# InputChannel_1.net
KiCad netlist of a schematic drawn in Altium Designer
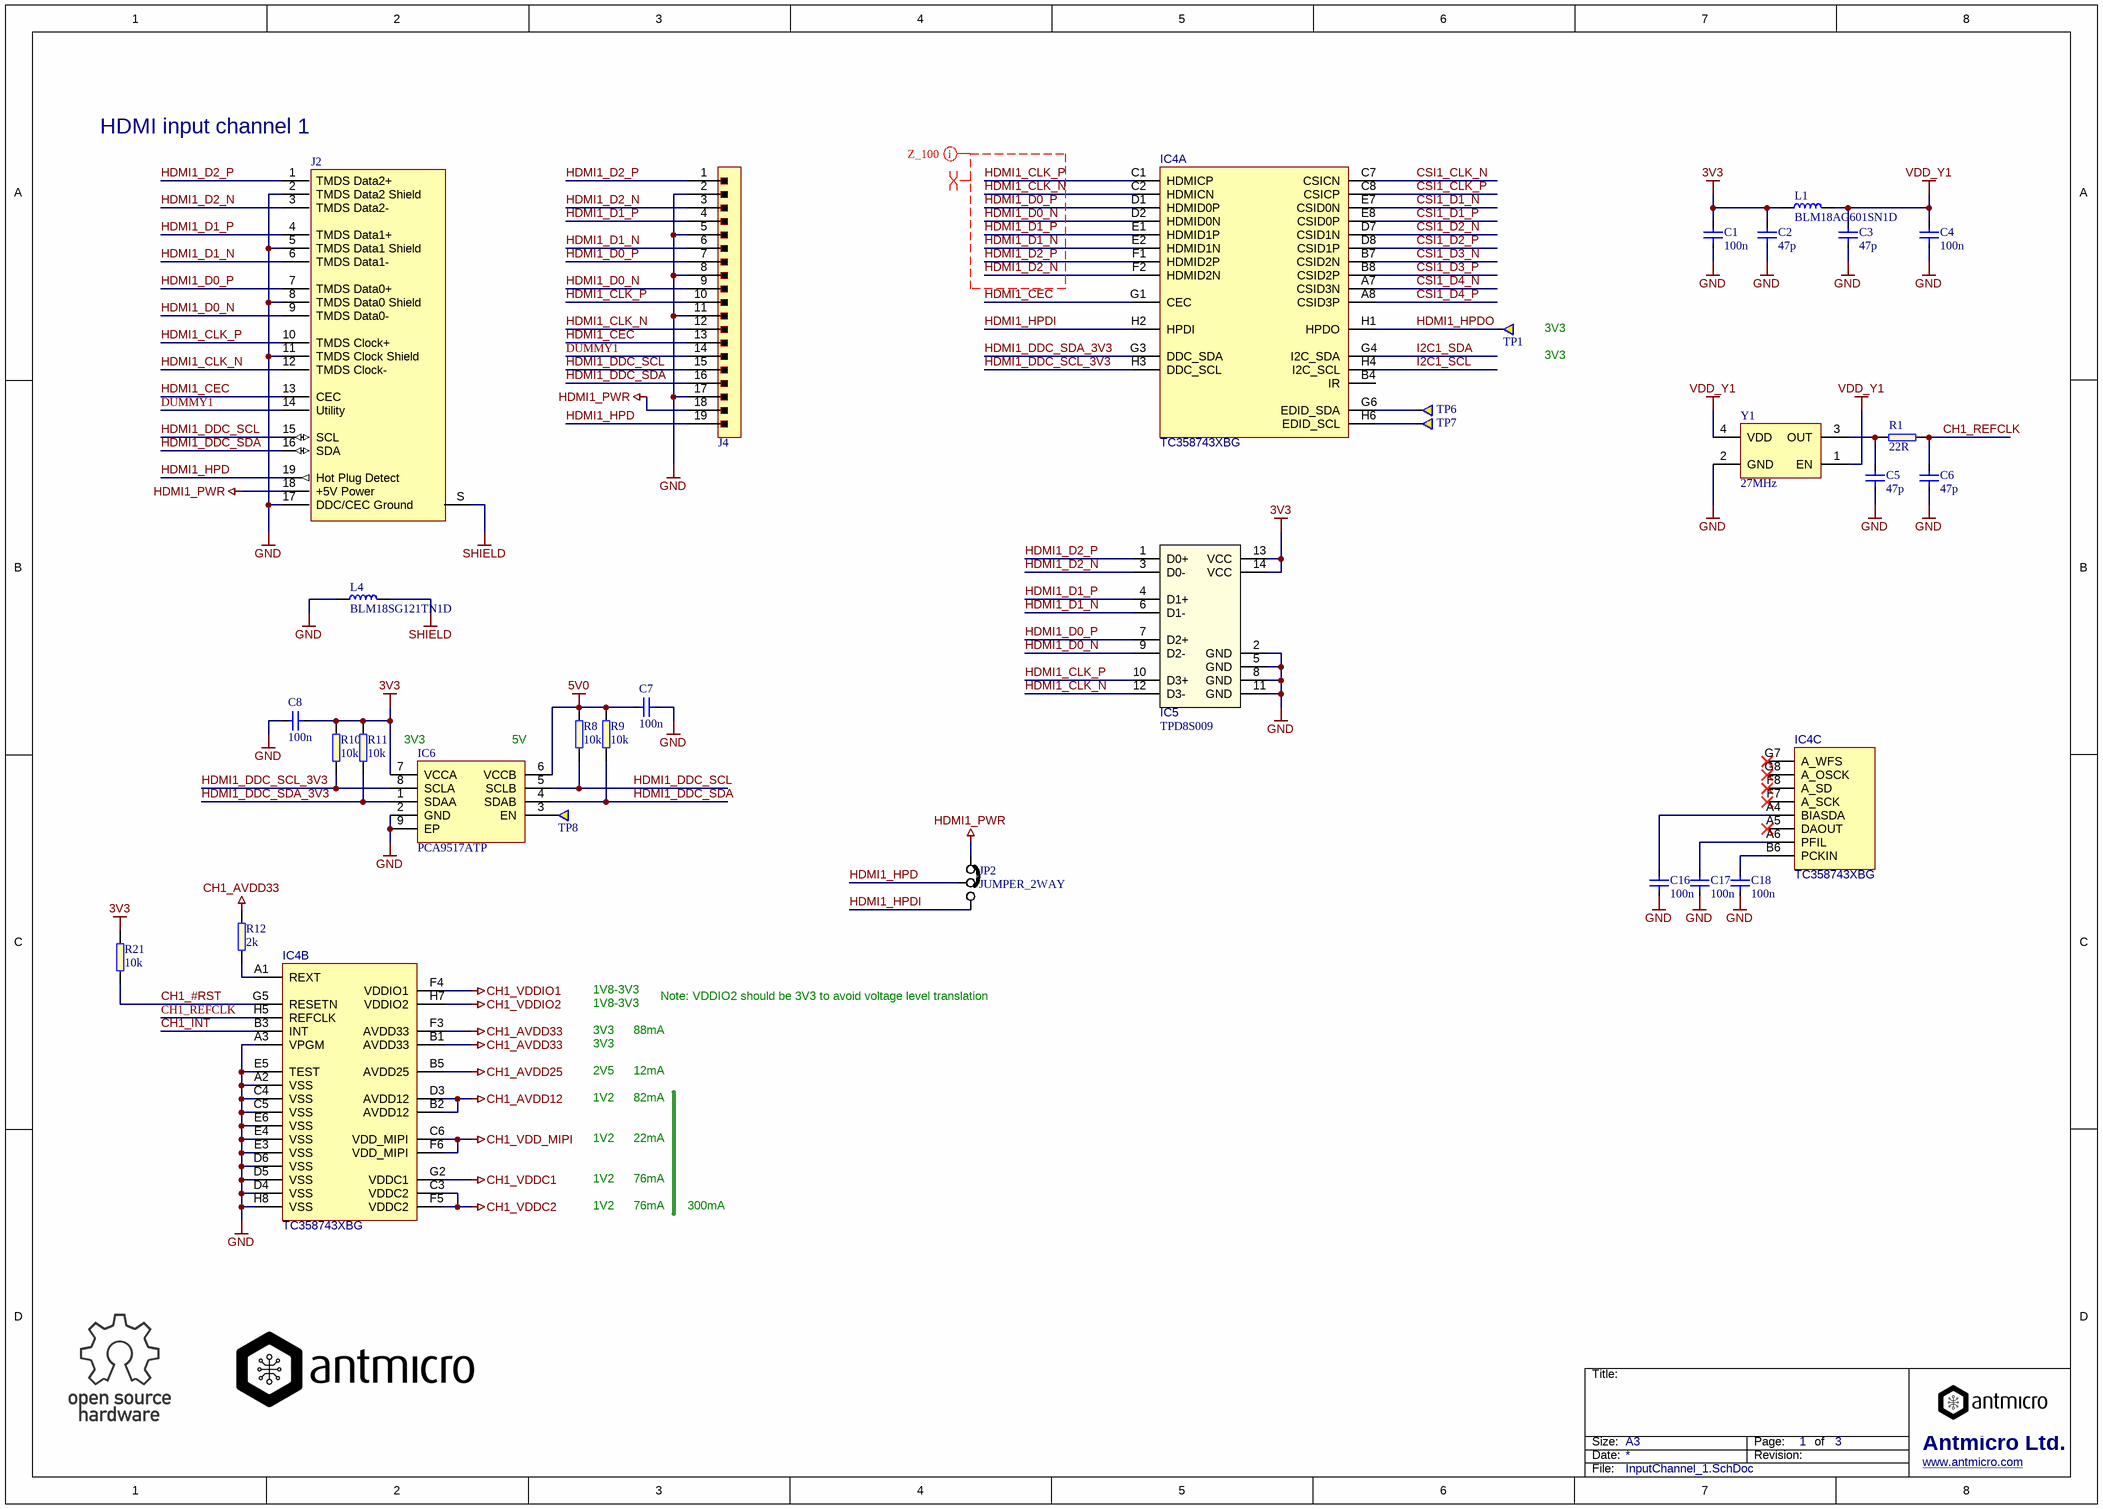
[diagram p0: InputChannel_1.SchDoc]

(export (version "E")
  (design (tool "Eeschema 10.0.6"))
  (components
    (comp (ref "C1")
      (value "100n")
      (footprint "HDMI-MIPI-Bridge:0402")
      (description "MLCC SMT Capacitor 100nF 0402")
      (fields (field (name "PART NUMBER") "C_100n_0402") (field (name "MANUFACTURER") "MULTICOMP"))
      (libsource (lib "AntmicroComponents") (part "C"))
    )
    (comp (ref "C2")
      (value "47p")
      (footprint "HDMI-MIPI-Bridge:0402")
      (description "MLCC SMT Capacitor 47pF 0402")
      (fields (field (name "PART NUMBER") "C_47p_0402") (field (name "MANUFACTURER") "KEMET"))
      (libsource (lib "AntmicroComponents") (part "C"))
    )
    (comp (ref "C3")
      (value "47p")
      (footprint "HDMI-MIPI-Bridge:0402")
      (description "MLCC SMT Capacitor 47pF 0402")
      (fields (field (name "PART NUMBER") "C_47p_0402") (field (name "MANUFACTURER") "KEMET"))
      (libsource (lib "AntmicroComponents") (part "C"))
    )
    (comp (ref "C4")
      (value "100n")
      (footprint "HDMI-MIPI-Bridge:0402")
      (description "MLCC SMT Capacitor 100nF 0402")
      (fields (field (name "PART NUMBER") "C_100n_0402") (field (name "MANUFACTURER") "MULTICOMP"))
      (libsource (lib "AntmicroComponents") (part "C"))
    )
    (comp (ref "C5")
      (value "47p")
      (footprint "HDMI-MIPI-Bridge:0402")
      (description "MLCC SMT Capacitor 47pF 0402")
      (fields (field (name "PART NUMBER") "C_47p_0402") (field (name "MANUFACTURER") "KEMET"))
      (libsource (lib "AntmicroComponents") (part "C"))
    )
    (comp (ref "C6")
      (value "47p")
      (footprint "HDMI-MIPI-Bridge:0402")
      (description "MLCC SMT Capacitor 47pF 0402")
      (fields (field (name "PART NUMBER") "C_47p_0402") (field (name "MANUFACTURER") "KEMET"))
      (libsource (lib "AntmicroComponents") (part "C"))
    )
    (comp (ref "C7")
      (value "100n")
      (footprint "HDMI-MIPI-Bridge:0402")
      (description "MLCC SMT Capacitor 100nF 0402")
      (fields (field (name "PART NUMBER") "C_100n_0402") (field (name "MANUFACTURER") "MULTICOMP"))
      (libsource (lib "AntmicroComponents") (part "C"))
    )
    (comp (ref "C8")
      (value "100n")
      (footprint "HDMI-MIPI-Bridge:0402")
      (description "MLCC SMT Capacitor 100nF 0402")
      (fields (field (name "PART NUMBER") "C_100n_0402") (field (name "MANUFACTURER") "MULTICOMP"))
      (libsource (lib "AntmicroComponents") (part "C"))
    )
    (comp (ref "C16")
      (value "100n")
      (footprint "HDMI-MIPI-Bridge:0402")
      (description "MLCC SMT Capacitor 100nF 0402")
      (fields (field (name "PART NUMBER") "C_100n_0402") (field (name "MANUFACTURER") "MULTICOMP"))
      (libsource (lib "AntmicroComponents") (part "C"))
    )
    (comp (ref "C17")
      (value "100n")
      (footprint "HDMI-MIPI-Bridge:0402")
      (description "MLCC SMT Capacitor 100nF 0402")
      (fields (field (name "PART NUMBER") "C_100n_0402") (field (name "MANUFACTURER") "MULTICOMP"))
      (libsource (lib "AntmicroComponents") (part "C"))
    )
    (comp (ref "C18")
      (value "100n")
      (footprint "HDMI-MIPI-Bridge:0402")
      (description "MLCC SMT Capacitor 100nF 0402")
      (fields (field (name "PART NUMBER") "C_100n_0402") (field (name "MANUFACTURER") "MULTICOMP"))
      (libsource (lib "AntmicroComponents") (part "C"))
    )
    (comp (ref "IC4")
      (value "TC358743XBG")
      (footprint "HDMI-MIPI-Bridge:TC358743XBG")
      (description "Toshiba TC358743XBG HDMI-CSI bridge")
      (fields (field (name "MANUFACTURER") "Toshiba"))
      (libsource (lib "AntmicroComponents") (part "TC358743XBG"))
    )
    (comp (ref "IC5")
      (value "TPD8S009")
      (footprint "HDMI-MIPI-Bridge:SON-15")
      (description "8-Channel ESD Protection for DisplayPort and HDMI")
      (fields (field (name "MANUFACTURER") "TEXAS INSTRUMENTS") (field (name "MPN") "TPD8S009DSMR"))
      (libsource (lib "AntmicroComponents") (part "TPD8S009"))
    )
    (comp (ref "IC6")
      (value "PCA9517ATP")
      (footprint "HDMI-MIPI-Bridge:PCA9517ATP")
      (description "I2C BUS REPEATER W/ LEVEL TRANS, HWSON-8")
      (fields (field (name "MANUFACTURER") "NXP"))
      (libsource (lib "AntmicroComponents") (part "PCA9517ATP"))
    )
    (comp (ref "J2")
      (value "~")
      (footprint "HDMI-MIPI-Bridge:Molex_HDMI_471511001")
      (description "Header right angle HDMI")
      (fields (field (name "PART NUMBER") "CON-Molex-471511001") (field (name "MANUFACTURER") "MOLEX"))
      (libsource (lib "AntmicroComponents") (part "CON-Molex-471511001"))
    )
    (comp (ref "J4")
      (value "Molex-505110-1992")
      (footprint "HDMI-MIPI-Bridge:CON-Molex-505110-1992")
      (description "FPC socket 19 pins")
      (fields (field (name "PART NUMBER") "CON-Molex-505110-1992") (field (name "MANUFACTURER") "Molex"))
      (libsource (lib "AntmicroComponents") (part "1X19"))
    )
    (comp (ref "JP2")
      (value "JUMPER_2WAY")
      (footprint "HDMI-MIPI-Bridge:JUMPER_2WAY")
      (description "Solder jumper")
      (fields (field (name "PART NUMBER") "Jumper 2 way"))
      (libsource (lib "AntmicroComponents") (part "JUMPER_2WAY"))
    )
    (comp (ref "L1")
      (value "BLM18AG601SN1D")
      (footprint "HDMI-MIPI-Bridge:0603")
      (description "Ferrite Bead, 600 ohm, 0603 [1608 Metric], BLM18A Series, 500 mA, 0.38 ohm, ± 25%")
      (fields (field (name "MANUFACTURER") "MURATA"))
      (libsource (lib "AntmicroComponents") (part "Inductor SMT"))
    )
    (comp (ref "L4")
      (value "BLM18SG121TN1D")
      (footprint "HDMI-MIPI-Bridge:0603")
      (description "FERRITE BEAD, 0.025OHM, 3A, 0603")
      (fields (field (name "MANUFACTURER") "MURATA"))
      (libsource (lib "AntmicroComponents") (part "Inductor SMT"))
    )
    (comp (ref "R1")
      (value "22R")
      (footprint "HDMI-MIPI-Bridge:0402")
      (description "SMT Resistor 22R 0402")
      (fields (field (name "PART NUMBER") "R_22R_0402") (field (name "MANUFACTURER") "VISHAY"))
      (libsource (lib "") (part "R_1"))
    )
    (comp (ref "R8")
      (value "10k")
      (footprint "HDMI-MIPI-Bridge:0402")
      (description "SMT Resistor 0402")
      (fields (field (name "PART NUMBER") "R_10k_0402") (field (name "MANUFACTURER") "MULTICOMP"))
      (libsource (lib "AntmicroComponents") (part "R"))
    )
    (comp (ref "R9")
      (value "10k")
      (footprint "HDMI-MIPI-Bridge:0402")
      (description "SMT Resistor 0402")
      (fields (field (name "PART NUMBER") "R_10k_0402") (field (name "MANUFACTURER") "MULTICOMP"))
      (libsource (lib "AntmicroComponents") (part "R"))
    )
    (comp (ref "R10")
      (value "10k")
      (footprint "HDMI-MIPI-Bridge:0402")
      (description "SMT Resistor 0402")
      (fields (field (name "PART NUMBER") "R_10k_0402") (field (name "MANUFACTURER") "MULTICOMP"))
      (libsource (lib "AntmicroComponents") (part "R"))
    )
    (comp (ref "R11")
      (value "10k")
      (footprint "HDMI-MIPI-Bridge:0402")
      (description "SMT Resistor 0402")
      (fields (field (name "PART NUMBER") "R_10k_0402") (field (name "MANUFACTURER") "MULTICOMP"))
      (libsource (lib "AntmicroComponents") (part "R"))
    )
    (comp (ref "R12")
      (value "2k")
      (footprint "HDMI-MIPI-Bridge:0603")
      (description "SMT Resistor 2k 0603")
      (fields (field (name "PART NUMBER") "R_2k_0603") (field (name "MANUFACTURER") "MULTICOMP"))
      (libsource (lib "AntmicroComponents") (part "R"))
    )
    (comp (ref "R21")
      (value "10k")
      (footprint "HDMI-MIPI-Bridge:0402")
      (description "SMT Resistor 0402")
      (fields (field (name "PART NUMBER") "R_10k_0402") (field (name "MANUFACTURER") "MULTICOMP"))
      (libsource (lib "AntmicroComponents") (part "R"))
    )
    (comp (ref "TP1")
      (value "Testpad")
      (footprint "HDMI-MIPI-Bridge:TP-R-1")
      (description "Testpad, round, 1mm")
      (fields (field (name "PART NUMBER") "TP-R-1"))
      (libsource (lib "AntmicroComponents") (part "Testpad"))
    )
    (comp (ref "TP6")
      (value "Testpad")
      (footprint "HDMI-MIPI-Bridge:TP-R-1")
      (description "Testpad, round, 1mm")
      (fields (field (name "PART NUMBER") "TP-R-1"))
      (libsource (lib "AntmicroComponents") (part "Testpad"))
    )
    (comp (ref "TP7")
      (value "Testpad")
      (footprint "HDMI-MIPI-Bridge:TP-R-1")
      (description "Testpad, round, 1mm")
      (fields (field (name "PART NUMBER") "TP-R-1"))
      (libsource (lib "AntmicroComponents") (part "Testpad"))
    )
    (comp (ref "TP8")
      (value "Testpad")
      (footprint "HDMI-MIPI-Bridge:TP-R-1")
      (description "Testpad, round, 1mm")
      (fields (field (name "PART NUMBER") "TP-R-1"))
      (libsource (lib "AntmicroComponents") (part "Testpad"))
    )
    (comp (ref "Y1")
      (value "27MHz")
      (footprint "HDMI-MIPI-Bridge:TXC_7C")
      (description "OSC, 27.000MHZ, 3.3V, SMD, 5.0X3.2")
      (fields (field (name "PART NUMBER") "7C-27.000MBB-T") (field (name "MANUFACTURER") "TXC"))
      (libsource (lib "AntmicroComponents") (part "TXC_7C"))
    )
  )
  (nets
    (net (code "1") (name "/CH1_#RST") (class "Default")
      (node (ref "IC4") (pin "G5") (pinfunction "RESETN_G5") (pintype "passive"))
      (node (ref "R21") (pin "1") (pintype "passive"))
    )
    (net (code "2") (name "/CH1_INT") (class "Default")
      (node (ref "IC4") (pin "B3") (pinfunction "INT_B3") (pintype "passive"))
    )
    (net (code "3") (name "/CH1_REFCLK") (class "Default")
      (node (ref "C6") (pin "2") (pinfunction "2_2") (pintype "passive"))
      (node (ref "IC4") (pin "H5") (pinfunction "REFCLK_H5") (pintype "passive"))
      (node (ref "R1") (pin "2") (pintype "passive"))
    )
    (net (code "4") (name "/CSI1_CLK_N") (class "Default")
      (node (ref "IC4") (pin "C7") (pinfunction "CSICN_C7") (pintype "passive"))
    )
    (net (code "5") (name "/CSI1_CLK_P") (class "Default")
      (node (ref "IC4") (pin "C8") (pinfunction "CSICP_C8") (pintype "passive"))
    )
    (net (code "6") (name "/CSI1_D1_N") (class "Default")
      (node (ref "IC4") (pin "E7") (pinfunction "CSID0N_E7") (pintype "passive"))
    )
    (net (code "7") (name "/CSI1_D1_P") (class "Default")
      (node (ref "IC4") (pin "E8") (pinfunction "CSID0P_E8") (pintype "passive"))
    )
    (net (code "8") (name "/CSI1_D2_N") (class "Default")
      (node (ref "IC4") (pin "D7") (pinfunction "CSID1N_D7") (pintype "passive"))
    )
    (net (code "9") (name "/CSI1_D2_P") (class "Default")
      (node (ref "IC4") (pin "D8") (pinfunction "CSID1P_D8") (pintype "passive"))
    )
    (net (code "10") (name "/CSI1_D3_N") (class "Default")
      (node (ref "IC4") (pin "B7") (pinfunction "CSID2N_B7") (pintype "passive"))
    )
    (net (code "11") (name "/CSI1_D3_P") (class "Default")
      (node (ref "IC4") (pin "B8") (pinfunction "CSID2P_B8") (pintype "passive"))
    )
    (net (code "12") (name "/CSI1_D4_N") (class "Default")
      (node (ref "IC4") (pin "A7") (pinfunction "CSID3N_A7") (pintype "passive"))
    )
    (net (code "13") (name "/CSI1_D4_P") (class "Default")
      (node (ref "IC4") (pin "A8") (pinfunction "CSID3P_A8") (pintype "passive"))
    )
    (net (code "14") (name "/DUMMY1") (class "Default")
      (node (ref "J2") (pin "14") (pinfunction "Utility_14") (pintype "passive"))
      (node (ref "J4") (pin "14") (pinfunction "14_14") (pintype "passive"))
    )
    (net (code "15") (name "/HDMI1_CEC") (class "Default")
      (node (ref "IC4") (pin "G1") (pinfunction "CEC_G1") (pintype "passive"))
      (node (ref "J2") (pin "13") (pinfunction "CEC_13") (pintype "passive"))
      (node (ref "J4") (pin "13") (pinfunction "13_13") (pintype "passive"))
    )
    (net (code "16") (name "/HDMI1_CLK_N") (class "Default")
      (node (ref "IC4") (pin "C2") (pinfunction "HDMICN_C2") (pintype "passive"))
      (node (ref "IC5") (pin "12") (pinfunction "D3-_12") (pintype "passive"))
      (node (ref "J2") (pin "12") (pinfunction "TMDS_Clock-_12") (pintype "passive"))
      (node (ref "J4") (pin "12") (pinfunction "12_12") (pintype "passive"))
    )
    (net (code "17") (name "/HDMI1_CLK_P") (class "Default")
      (node (ref "IC4") (pin "C1") (pinfunction "HDMICP_C1") (pintype "passive"))
      (node (ref "IC5") (pin "10") (pinfunction "D3+_10") (pintype "passive"))
      (node (ref "J2") (pin "10") (pinfunction "TMDS_Clock+_10") (pintype "passive"))
      (node (ref "J4") (pin "10") (pinfunction "10_10") (pintype "passive"))
    )
    (net (code "18") (name "/HDMI1_D0_N") (class "Default")
      (node (ref "IC4") (pin "D2") (pinfunction "HDMID0N_D2") (pintype "passive"))
      (node (ref "IC5") (pin "9") (pinfunction "D2-_9") (pintype "passive"))
      (node (ref "J2") (pin "9") (pinfunction "TMDS_Data0-_9") (pintype "passive"))
      (node (ref "J4") (pin "9") (pinfunction "9_9") (pintype "passive"))
    )
    (net (code "19") (name "/HDMI1_D0_P") (class "Default")
      (node (ref "IC4") (pin "D1") (pinfunction "HDMID0P_D1") (pintype "passive"))
      (node (ref "IC5") (pin "7") (pinfunction "D2+_7") (pintype "passive"))
      (node (ref "J2") (pin "7") (pinfunction "TMDS_Data0+_7") (pintype "passive"))
      (node (ref "J4") (pin "7") (pinfunction "7_7") (pintype "passive"))
    )
    (net (code "20") (name "/HDMI1_D1_N") (class "Default")
      (node (ref "IC4") (pin "E2") (pinfunction "HDMID1N_E2") (pintype "passive"))
      (node (ref "IC5") (pin "6") (pinfunction "D1-_6") (pintype "passive"))
      (node (ref "J2") (pin "6") (pinfunction "TMDS_Data1-_6") (pintype "passive"))
      (node (ref "J4") (pin "6") (pinfunction "6_6") (pintype "passive"))
    )
    (net (code "21") (name "/HDMI1_D1_P") (class "Default")
      (node (ref "IC4") (pin "E1") (pinfunction "HDMID1P_E1") (pintype "passive"))
      (node (ref "IC5") (pin "4") (pinfunction "D1+_4") (pintype "passive"))
      (node (ref "J2") (pin "4") (pinfunction "TMDS_Data1+_4") (pintype "passive"))
      (node (ref "J4") (pin "4") (pinfunction "4_4") (pintype "passive"))
    )
    (net (code "22") (name "/HDMI1_D2_N") (class "Default")
      (node (ref "IC4") (pin "F2") (pinfunction "HDMID2N_F2") (pintype "passive"))
      (node (ref "IC5") (pin "3") (pinfunction "D0-_3") (pintype "passive"))
      (node (ref "J2") (pin "3") (pinfunction "TMDS_Data2-_3") (pintype "passive"))
      (node (ref "J4") (pin "3") (pinfunction "3_3") (pintype "passive"))
    )
    (net (code "23") (name "/HDMI1_D2_P") (class "Default")
      (node (ref "IC4") (pin "F1") (pinfunction "HDMID2P_F1") (pintype "passive"))
      (node (ref "IC5") (pin "1") (pinfunction "D0+_1") (pintype "passive"))
      (node (ref "J2") (pin "1") (pinfunction "TMDS_Data2+_1") (pintype "passive"))
      (node (ref "J4") (pin "1") (pinfunction "1_1") (pintype "passive"))
    )
    (net (code "24") (name "/HDMI1_DDC_SCL") (class "Default")
      (node (ref "IC6") (pin "5") (pinfunction "SCLB_5") (pintype "passive"))
      (node (ref "J2") (pin "15") (pinfunction "SCL_15") (pintype "bidirectional"))
      (node (ref "J4") (pin "15") (pinfunction "15_15") (pintype "passive"))
      (node (ref "R8") (pin "1") (pintype "passive"))
    )
    (net (code "25") (name "/HDMI1_DDC_SCL_3V3") (class "Default")
      (node (ref "IC4") (pin "H3") (pinfunction "DDC_SCL_H3") (pintype "passive"))
      (node (ref "IC6") (pin "8") (pinfunction "SCLA_8") (pintype "passive"))
      (node (ref "R10") (pin "1") (pintype "passive"))
    )
    (net (code "26") (name "/HDMI1_DDC_SDA") (class "Default")
      (node (ref "IC6") (pin "4") (pinfunction "SDAB_4") (pintype "passive"))
      (node (ref "J2") (pin "16") (pinfunction "SDA_16") (pintype "bidirectional"))
      (node (ref "J4") (pin "16") (pinfunction "16_16") (pintype "passive"))
      (node (ref "R9") (pin "1") (pintype "passive"))
    )
    (net (code "27") (name "/HDMI1_DDC_SDA_3V3") (class "Default")
      (node (ref "IC4") (pin "G3") (pinfunction "DDC_SDA_G3") (pintype "passive"))
      (node (ref "IC6") (pin "1") (pinfunction "SDAA_1") (pintype "passive"))
      (node (ref "R11") (pin "1") (pintype "passive"))
    )
    (net (code "28") (name "/HDMI1_HPD") (class "Default")
      (node (ref "J2") (pin "19") (pinfunction "Hot_Plug_Detect_19") (pintype "output"))
      (node (ref "J4") (pin "19") (pinfunction "19_19") (pintype "passive"))
      (node (ref "JP2") (pin "2") (pinfunction "2_2") (pintype "passive"))
    )
    (net (code "29") (name "/HDMI1_HPDI") (class "Default")
      (node (ref "IC4") (pin "H2") (pinfunction "HPDI_H2") (pintype "passive"))
      (node (ref "JP2") (pin "3") (pinfunction "3_3") (pintype "passive"))
    )
    (net (code "30") (name "/HDMI1_HPDO") (class "Default")
      (node (ref "IC4") (pin "H1") (pinfunction "HPDO_H1") (pintype "passive"))
      (node (ref "TP1") (pin "1") (pintype "passive"))
    )
    (net (code "31") (name "/I2C1_SCL") (class "Default")
      (node (ref "IC4") (pin "H4") (pinfunction "I2C_SCL_H4") (pintype "passive"))
    )
    (net (code "32") (name "/I2C1_SDA") (class "Default")
      (node (ref "IC4") (pin "G4") (pinfunction "I2C_SDA_G4") (pintype "passive"))
    )
    (net (code "33") (name "3V3") (class "Default")
      (node (ref "C1") (pin "2") (pinfunction "2_2") (pintype "passive"))
      (node (ref "C2") (pin "2") (pinfunction "2_2") (pintype "passive"))
      (node (ref "C8") (pin "1") (pinfunction "1_1") (pintype "passive"))
      (node (ref "IC5") (pin "13") (pinfunction "VCC_13") (pintype "passive"))
      (node (ref "IC5") (pin "14") (pinfunction "VCC_14") (pintype "passive"))
      (node (ref "IC6") (pin "7") (pinfunction "VCCA_7") (pintype "passive"))
      (node (ref "L1") (pin "1") (pintype "passive"))
      (node (ref "R10") (pin "2") (pintype "passive"))
      (node (ref "R11") (pin "2") (pintype "passive"))
      (node (ref "R21") (pin "2") (pintype "passive"))
    )
    (net (code "34") (name "5V0") (class "Default")
      (node (ref "C7") (pin "2") (pinfunction "2_2") (pintype "passive"))
      (node (ref "IC6") (pin "6") (pinfunction "VCCB_6") (pintype "passive"))
      (node (ref "R8") (pin "2") (pintype "passive"))
      (node (ref "R9") (pin "2") (pintype "passive"))
    )
    (net (code "35") (name "CH1_AVDD12") (class "Default")
      (node (ref "IC4") (pin "B2") (pinfunction "AVDD12_B2") (pintype "passive"))
      (node (ref "IC4") (pin "D3") (pinfunction "AVDD12_D3") (pintype "passive"))
    )
    (net (code "36") (name "CH1_AVDD25") (class "Default")
      (node (ref "IC4") (pin "B5") (pinfunction "AVDD25_B5") (pintype "passive"))
    )
    (net (code "37") (name "CH1_AVDD33") (class "Default")
      (node (ref "IC4") (pin "B1") (pinfunction "AVDD33_B1") (pintype "passive"))
      (node (ref "IC4") (pin "F3") (pinfunction "AVDD33_F3") (pintype "passive"))
      (node (ref "R12") (pin "2") (pintype "passive"))
    )
    (net (code "38") (name "CH1_VDDC1") (class "Default")
      (node (ref "IC4") (pin "G2") (pinfunction "VDDC1_G2") (pintype "passive"))
    )
    (net (code "39") (name "CH1_VDDC2") (class "Default")
      (node (ref "IC4") (pin "C3") (pinfunction "VDDC2_C3") (pintype "passive"))
      (node (ref "IC4") (pin "F5") (pinfunction "VDDC2_F5") (pintype "passive"))
    )
    (net (code "40") (name "CH1_VDDIO1") (class "Default")
      (node (ref "IC4") (pin "F4") (pinfunction "VDDIO1_F4") (pintype "passive"))
    )
    (net (code "41") (name "CH1_VDDIO2") (class "Default")
      (node (ref "IC4") (pin "H7") (pinfunction "VDDIO2_H7") (pintype "passive"))
    )
    (net (code "42") (name "CH1_VDD_MIPI") (class "Default")
      (node (ref "IC4") (pin "C6") (pinfunction "VDD_MIPI_C6") (pintype "passive"))
      (node (ref "IC4") (pin "F6") (pinfunction "VDD_MIPI_F6") (pintype "passive"))
    )
    (net (code "43") (name "GND") (class "Default")
      (node (ref "C1") (pin "1") (pinfunction "1_1") (pintype "passive"))
      (node (ref "C16") (pin "1") (pinfunction "1_1") (pintype "passive"))
      (node (ref "C17") (pin "1") (pinfunction "1_1") (pintype "passive"))
      (node (ref "C18") (pin "1") (pinfunction "1_1") (pintype "passive"))
      (node (ref "C2") (pin "1") (pinfunction "1_1") (pintype "passive"))
      (node (ref "C3") (pin "1") (pinfunction "1_1") (pintype "passive"))
      (node (ref "C4") (pin "1") (pinfunction "1_1") (pintype "passive"))
      (node (ref "C5") (pin "1") (pinfunction "1_1") (pintype "passive"))
      (node (ref "C6") (pin "1") (pinfunction "1_1") (pintype "passive"))
      (node (ref "C7") (pin "1") (pinfunction "1_1") (pintype "passive"))
      (node (ref "C8") (pin "2") (pinfunction "2_2") (pintype "passive"))
      (node (ref "IC4") (pin "A2") (pinfunction "VSS_A2") (pintype "passive"))
      (node (ref "IC4") (pin "A3") (pinfunction "VPGM_A3") (pintype "passive"))
      (node (ref "IC4") (pin "C4") (pinfunction "VSS_C4") (pintype "passive"))
      (node (ref "IC4") (pin "C5") (pinfunction "VSS_C5") (pintype "passive"))
      (node (ref "IC4") (pin "D4") (pinfunction "VSS_D4") (pintype "passive"))
      (node (ref "IC4") (pin "D5") (pinfunction "VSS_D5") (pintype "passive"))
      (node (ref "IC4") (pin "D6") (pinfunction "VSS_D6") (pintype "passive"))
      (node (ref "IC4") (pin "E3") (pinfunction "VSS_E3") (pintype "passive"))
      (node (ref "IC4") (pin "E4") (pinfunction "VSS_E4") (pintype "passive"))
      (node (ref "IC4") (pin "E5") (pinfunction "TEST_E5") (pintype "passive"))
      (node (ref "IC4") (pin "E6") (pinfunction "VSS_E6") (pintype "passive"))
      (node (ref "IC4") (pin "H8") (pinfunction "VSS_H8") (pintype "passive"))
      (node (ref "IC5") (pin "11") (pinfunction "GND_11") (pintype "passive"))
      (node (ref "IC5") (pin "2") (pinfunction "GND_2") (pintype "passive"))
      (node (ref "IC5") (pin "5") (pinfunction "GND_5") (pintype "passive"))
      (node (ref "IC5") (pin "8") (pinfunction "GND_8") (pintype "passive"))
      (node (ref "IC6") (pin "2") (pinfunction "GND_2") (pintype "passive"))
      (node (ref "IC6") (pin "9") (pinfunction "EP_9") (pintype "passive"))
      (node (ref "J2") (pin "11") (pinfunction "TMDS_Clock_Shield_11") (pintype "passive"))
      (node (ref "J2") (pin "17") (pinfunction "DDC/CEC_Ground_17") (pintype "power_in"))
      (node (ref "J2") (pin "2") (pinfunction "TMDS_Data2_Shield_2") (pintype "passive"))
      (node (ref "J2") (pin "5") (pinfunction "TMDS_Data1_Shield_5") (pintype "passive"))
      (node (ref "J2") (pin "8") (pinfunction "TMDS_Data0_Shield_8") (pintype "passive"))
      (node (ref "J4") (pin "11") (pinfunction "11_11") (pintype "passive"))
      (node (ref "J4") (pin "17") (pinfunction "17_17") (pintype "passive"))
      (node (ref "J4") (pin "2") (pinfunction "2_2") (pintype "passive"))
      (node (ref "J4") (pin "5") (pinfunction "5_5") (pintype "passive"))
      (node (ref "J4") (pin "8") (pinfunction "8_8") (pintype "passive"))
      (node (ref "L4") (pin "1") (pintype "passive"))
      (node (ref "Y1") (pin "2") (pinfunction "GND_2") (pintype "passive"))
    )
    (net (code "44") (name "HDMI1_PWR") (class "Default")
      (node (ref "J2") (pin "18") (pinfunction "+5V_Power_18") (pintype "power_in"))
      (node (ref "J4") (pin "18") (pinfunction "18_18") (pintype "passive"))
      (node (ref "JP2") (pin "1") (pinfunction "1_1") (pintype "passive"))
    )
    (net (code "45") (name "Net-(IC4A-EDID_SCL)") (class "Default")
      (node (ref "IC4") (pin "H6") (pinfunction "EDID_SCL_H6") (pintype "passive"))
      (node (ref "TP7") (pin "1") (pintype "passive"))
    )
    (net (code "46") (name "Net-(IC4A-EDID_SDA)") (class "Default")
      (node (ref "IC4") (pin "G6") (pinfunction "EDID_SDA_G6") (pintype "passive"))
      (node (ref "TP6") (pin "1") (pintype "passive"))
    )
    (net (code "47") (name "Net-(IC4B-REXT)") (class "Default")
      (node (ref "IC4") (pin "A1") (pinfunction "REXT_A1") (pintype "passive"))
      (node (ref "R12") (pin "1") (pintype "passive"))
    )
    (net (code "48") (name "Net-(IC4C-BIASDA)") (class "Default")
      (node (ref "C16") (pin "2") (pinfunction "2_2") (pintype "passive"))
      (node (ref "IC4") (pin "A4") (pinfunction "BIASDA_A4") (pintype "passive"))
    )
    (net (code "49") (name "Net-(IC4C-PCKIN)") (class "Default")
      (node (ref "C18") (pin "2") (pinfunction "2_2") (pintype "passive"))
      (node (ref "IC4") (pin "B6") (pinfunction "PCKIN_B6") (pintype "passive"))
    )
    (net (code "50") (name "Net-(IC4C-PFIL)") (class "Default")
      (node (ref "C17") (pin "2") (pinfunction "2_2") (pintype "passive"))
      (node (ref "IC4") (pin "A6") (pinfunction "PFIL_A6") (pintype "passive"))
    )
    (net (code "51") (name "Net-(IC6-EN)") (class "Default")
      (node (ref "IC6") (pin "3") (pinfunction "EN_3") (pintype "passive"))
      (node (ref "TP8") (pin "1") (pintype "passive"))
    )
    (net (code "52") (name "Net-(Y1-OUT)") (class "Default")
      (node (ref "C5") (pin "2") (pinfunction "2_2") (pintype "passive"))
      (node (ref "R1") (pin "1") (pintype "passive"))
      (node (ref "Y1") (pin "3") (pinfunction "OUT_3") (pintype "passive"))
    )
    (net (code "53") (name "SHIELD") (class "Default")
      (node (ref "J2") (pin "S") (pinfunction "SH_S") (pintype "passive"))
      (node (ref "L4") (pin "2") (pintype "passive"))
    )
    (net (code "54") (name "VDD_Y1") (class "Default")
      (node (ref "C3") (pin "2") (pinfunction "2_2") (pintype "passive"))
      (node (ref "C4") (pin "2") (pinfunction "2_2") (pintype "passive"))
      (node (ref "L1") (pin "2") (pintype "passive"))
      (node (ref "Y1") (pin "1") (pinfunction "EN_1") (pintype "passive"))
      (node (ref "Y1") (pin "4") (pinfunction "VDD_4") (pintype "passive"))
    )
    (net (code "55") (name "unconnected-(IC4A-IR-PadB4)") (class "Default")
      (node (ref "IC4") (pin "B4") (pinfunction "IR_B4") (pintype "passive"))
    )
    (net (code "56") (name "unconnected-(IC4C-A_OSCK-PadG8)") (class "Default")
      (node (ref "IC4") (pin "G8") (pinfunction "A_OSCK_G8") (pintype "passive+no_connect"))
    )
    (net (code "57") (name "unconnected-(IC4C-A_SCK-PadF7)") (class "Default")
      (node (ref "IC4") (pin "F7") (pinfunction "A_SCK_F7") (pintype "passive+no_connect"))
    )
    (net (code "58") (name "unconnected-(IC4C-A_SD-PadF8)") (class "Default")
      (node (ref "IC4") (pin "F8") (pinfunction "A_SD_F8") (pintype "passive+no_connect"))
    )
    (net (code "59") (name "unconnected-(IC4C-A_WFS-PadG7)") (class "Default")
      (node (ref "IC4") (pin "G7") (pinfunction "A_WFS_G7") (pintype "passive+no_connect"))
    )
    (net (code "60") (name "unconnected-(IC4C-DAOUT-PadA5)") (class "Default")
      (node (ref "IC4") (pin "A5") (pinfunction "DAOUT_A5") (pintype "passive+no_connect"))
    )
  )
)
